# SPI_ROM.net
KiCad netlist of a schematic drawn in Altium Designer
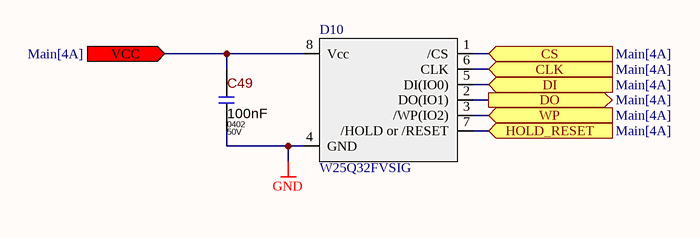
[diagram p0: SPI_ROM.SchDoc]

(export (version "E")
  (design (tool "Eeschema 10.0.6"))
  (components
    (comp (ref "C49")
      (value "100nF")
      (footprint "Cap_0402")
      (description "100nF 50V  ±25% 0402 Ceramic Capacitor")
      (fields
        (field (name "TOLERANCE") "±25%")
        (field (name "PACKAGE") "0402")
        (field (name "VOLTAGE") "50V")
      )
      (libsource (lib "Capacitors") (part "Cap_0402_100nF"))
    )
    (comp (ref "D10")
      (value "W25Q32FVSIG")
      (footprint "SOIC8")
      (description "SPI\\QSPI Flash 4MB")
      (libsource (lib "IC") (part "W25Q32FVSIG"))
    )
  )
  (nets
    (net (code "1") (name "/CLK") (class "Default")
      (node (ref "D10") (pin "6") (pinfunction "CLK_6") (pintype "passive"))
    )
    (net (code "2") (name "/CS") (class "Default")
      (node (ref "D10") (pin "1") (pinfunction "/CS_1") (pintype "passive"))
    )
    (net (code "3") (name "/DI") (class "Default")
      (node (ref "D10") (pin "5") (pinfunction "DI(IO0)_5") (pintype "passive"))
    )
    (net (code "4") (name "/DO") (class "Default")
      (node (ref "D10") (pin "2") (pinfunction "DO(IO1)_2") (pintype "passive"))
    )
    (net (code "5") (name "/HOLD_RESET") (class "Default")
      (node (ref "D10") (pin "7") (pinfunction "/HOLD_or_/RESET_7") (pintype "passive"))
    )
    (net (code "6") (name "/VCC") (class "Default")
      (node (ref "C49") (pin "1") (pinfunction "1_1") (pintype "passive"))
      (node (ref "D10") (pin "8") (pinfunction "Vcc_8") (pintype "passive"))
    )
    (net (code "7") (name "/WP") (class "Default")
      (node (ref "D10") (pin "3") (pinfunction "/WP(IO2)_3") (pintype "passive"))
    )
    (net (code "8") (name "GND") (class "Default")
      (node (ref "C49") (pin "2") (pinfunction "2_2") (pintype "passive"))
      (node (ref "D10") (pin "4") (pinfunction "GND_4") (pintype "passive"))
    )
  )
)
